# usb_smt.net
KiCad netlist of a schematic drawn in Altium Designer
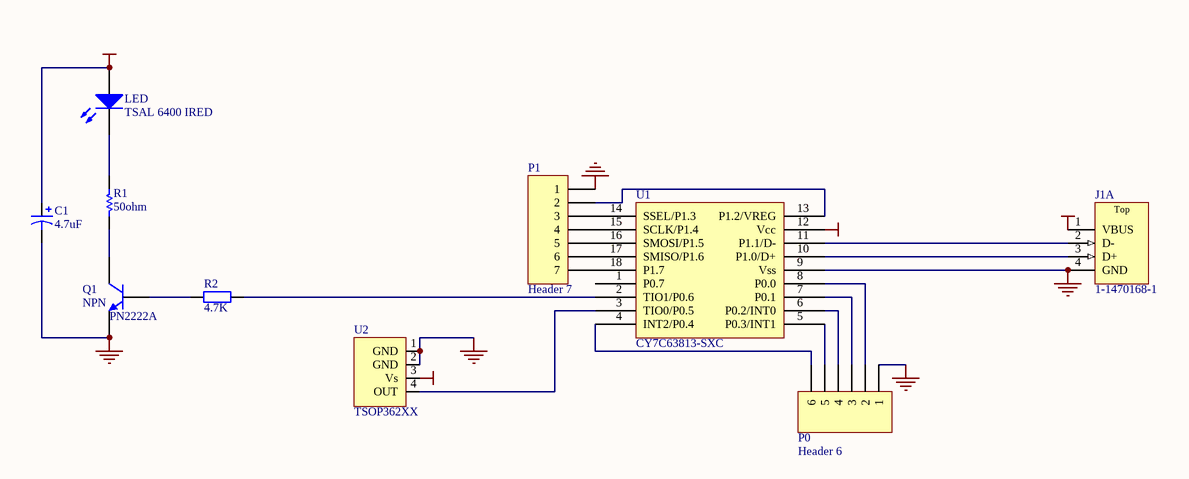
[diagram p0: usb_smt.SCHDOC]

(export (version "E")
  (design (tool "Eeschema 10.0.6"))
  (components
    (comp (ref "C1")
      (value "4.7uF")
      (footprint "TC3216-1206")
      (description "Polarized Capacitor (Radial)")
      (fields (field (name "Comment") "Cap Pol1") (field (name "PUBLISHER") "Altium Limited"))
      (libsource (lib "Miscellaneous Devices") (part "Cap Pol1"))
    )
    (comp (ref "J1")
      (value "1-1470168-1")
      (footprint "1470695")
      (description "USB 1.1, Right Angle, Thru-Hole, A Type, Receptacle, 4x4 Position, Stacked, Black")
      (fields (field (name "PUBLISHER") "Altium Limited"))
      (libsource (lib "AMP Serial Bus USB") (part "1-1470168-1"))
    )
    (comp (ref "LED")
      (value "TSAL 6400 IRED")
      (footprint "LED")
      (description "Typical INFRARED GaAs LED")
      (fields (field (name "PUBLISHER") "Altium Limited"))
      (libsource (lib "Miscellaneous Devices") (part "LED0"))
    )
    (comp (ref "P0")
      (value "Header 6")
      (footprint "HDR1X6")
      (description "Header, 6-Pin")
      (fields (field (name "PUBLISHER") "Altium Limited"))
      (libsource (lib "Miscellaneous Connectors") (part "Header 6"))
    )
    (comp (ref "P1")
      (value "Header 7")
      (footprint "HDR1X7")
      (description "Header, 7-Pin")
      (fields (field (name "PUBLISHER") "Altium Limited"))
      (libsource (lib "Miscellaneous Connectors") (part "Header 7"))
    )
    (comp (ref "Q1")
      (value "NPN")
      (footprint "SO-G3/D4.1")
      (description "NPN Bipolar Transistor")
      (fields (field (name "PUBLISHER") "Altium Limited"))
      (libsource (lib "Miscellaneous Devices") (part "NPN"))
    )
    (comp (ref "R1")
      (value "50ohm")
      (footprint "CR1608-0603")
      (description "Semiconductor Resistor")
      (fields (field (name "PUBLISHER") "Altium Limited"))
      (libsource (lib "Miscellaneous Devices") (part "Res Semi"))
    )
    (comp (ref "R2")
      (value "4.7K")
      (footprint "CR1608-0603")
      (description "Resistor")
      (fields (field (name "Comment") "Res2") (field (name "PUBLISHER") "Altium Limited"))
      (libsource (lib "Miscellaneous Devices") (part "Res2"))
    )
    (comp (ref "U1")
      (value "CY7C63813-SXC")
      (footprint "SO-G18/E6.2")
      (description "USB microcontroller, SMT")
      (libsource (lib "ir") (part "CY7C63813-SXC"))
    )
    (comp (ref "U2") (value "TSOP362XX") (footprint "TSOP 362XX") (libsource (lib "ir") (part "TSOP36238")))
  )
  (nets
    (net (code "1") (name "GND") (class "Default")
      (node (ref "C1") (pin "2") (pinfunction "2_2") (pintype "passive"))
      (node (ref "J1") (pin "4") (pinfunction "GND_4") (pintype "power_in"))
      (node (ref "P0") (pin "1") (pinfunction "1_1") (pintype "passive"))
      (node (ref "P1") (pin "1") (pinfunction "1_1") (pintype "passive"))
      (node (ref "Q1") (pin "3") (pinfunction "E_3") (pintype "passive"))
      (node (ref "U1") (pin "9") (pinfunction "Vss_9") (pintype "passive"))
      (node (ref "U2") (pin "1") (pinfunction "GND_1") (pintype "passive"))
      (node (ref "U2") (pin "2") (pinfunction "GND_2") (pintype "passive"))
    )
    (net (code "2") (name "Net-(J1A-D+)") (class "Default")
      (node (ref "J1") (pin "3") (pinfunction "D+_3") (pintype "input"))
      (node (ref "U1") (pin "10") (pinfunction "P1.0/D+_10") (pintype "passive"))
    )
    (net (code "3") (name "Net-(J1A-D-)") (class "Default")
      (node (ref "J1") (pin "2") (pinfunction "D-_2") (pintype "input"))
      (node (ref "U1") (pin "11") (pinfunction "P1.1/D-_11") (pintype "passive"))
    )
    (net (code "4") (name "Net-(LED-K)") (class "Default")
      (node (ref "LED") (pin "2") (pinfunction "K_2") (pintype "passive"))
      (node (ref "R1") (pin "2") (pinfunction "2_2") (pintype "passive"))
    )
    (net (code "5") (name "Net-(Q1-B)") (class "Default")
      (node (ref "Q1") (pin "2") (pinfunction "B_2") (pintype "passive"))
      (node (ref "R2") (pin "2") (pinfunction "2_2") (pintype "passive"))
    )
    (net (code "6") (name "Net-(Q1-C)") (class "Default")
      (node (ref "Q1") (pin "1") (pinfunction "C_1") (pintype "passive"))
      (node (ref "R1") (pin "1") (pinfunction "1_1") (pintype "passive"))
    )
    (net (code "7") (name "Net-(U1-INT2{slash}P0.4)") (class "Default")
      (node (ref "P0") (pin "6") (pinfunction "6_6") (pintype "passive"))
      (node (ref "U1") (pin "4") (pinfunction "INT2/P0.4_4") (pintype "passive"))
    )
    (net (code "8") (name "Net-(U1-P0.0)") (class "Default")
      (node (ref "P0") (pin "2") (pinfunction "2_2") (pintype "passive"))
      (node (ref "U1") (pin "8") (pinfunction "P0.0_8") (pintype "passive"))
    )
    (net (code "9") (name "Net-(U1-P0.1)") (class "Default")
      (node (ref "P0") (pin "3") (pinfunction "3_3") (pintype "passive"))
      (node (ref "U1") (pin "7") (pinfunction "P0.1_7") (pintype "passive"))
    )
    (net (code "10") (name "Net-(U1-P0.2{slash}INT0)") (class "Default")
      (node (ref "P0") (pin "4") (pinfunction "4_4") (pintype "passive"))
      (node (ref "U1") (pin "6") (pinfunction "P0.2/INT0_6") (pintype "passive"))
    )
    (net (code "11") (name "Net-(U1-P0.3{slash}INT1)") (class "Default")
      (node (ref "P0") (pin "5") (pinfunction "5_5") (pintype "passive"))
      (node (ref "U1") (pin "5") (pinfunction "P0.3/INT1_5") (pintype "passive"))
    )
    (net (code "12") (name "Net-(U1-P1.2{slash}VREG)") (class "Default")
      (node (ref "P1") (pin "2") (pinfunction "2_2") (pintype "passive"))
      (node (ref "U1") (pin "13") (pinfunction "P1.2/VREG_13") (pintype "passive"))
    )
    (net (code "13") (name "Net-(U1-P1.7)") (class "Default")
      (node (ref "P1") (pin "7") (pinfunction "7_7") (pintype "passive"))
      (node (ref "U1") (pin "18") (pinfunction "P1.7_18") (pintype "passive"))
    )
    (net (code "14") (name "Net-(U1-SCLK{slash}P1.4)") (class "Default")
      (node (ref "P1") (pin "4") (pinfunction "4_4") (pintype "passive"))
      (node (ref "U1") (pin "15") (pinfunction "SCLK/P1.4_15") (pintype "passive"))
    )
    (net (code "15") (name "Net-(U1-SMISO{slash}P1.6)") (class "Default")
      (node (ref "P1") (pin "6") (pinfunction "6_6") (pintype "passive"))
      (node (ref "U1") (pin "17") (pinfunction "SMISO/P1.6_17") (pintype "passive"))
    )
    (net (code "16") (name "Net-(U1-SMOSI{slash}P1.5)") (class "Default")
      (node (ref "P1") (pin "5") (pinfunction "5_5") (pintype "passive"))
      (node (ref "U1") (pin "16") (pinfunction "SMOSI/P1.5_16") (pintype "passive"))
    )
    (net (code "17") (name "Net-(U1-SSEL{slash}P1.3)") (class "Default")
      (node (ref "P1") (pin "3") (pinfunction "3_3") (pintype "passive"))
      (node (ref "U1") (pin "14") (pinfunction "SSEL/P1.3_14") (pintype "passive"))
    )
    (net (code "18") (name "Net-(U1-TIO0{slash}P0.5)") (class "Default")
      (node (ref "U1") (pin "3") (pinfunction "TIO0/P0.5_3") (pintype "passive"))
      (node (ref "U2") (pin "4") (pinfunction "OUT_4") (pintype "passive"))
    )
    (net (code "19") (name "Net-(U1-TIO1{slash}P0.6)") (class "Default")
      (node (ref "R2") (pin "1") (pinfunction "1_1") (pintype "passive"))
      (node (ref "U1") (pin "2") (pinfunction "TIO1/P0.6_2") (pintype "passive"))
    )
    (net (code "20") (name "VCC") (class "Default")
      (node (ref "C1") (pin "1") (pinfunction "1_1") (pintype "passive"))
      (node (ref "J1") (pin "1") (pinfunction "VBUS_1") (pintype "power_in"))
      (node (ref "LED") (pin "1") (pinfunction "A_1") (pintype "passive"))
      (node (ref "U1") (pin "12") (pinfunction "Vcc_12") (pintype "passive"))
      (node (ref "U2") (pin "3") (pinfunction "Vs_3") (pintype "passive"))
    )
    (net (code "21") (name "unconnected-(U1-P0.7-Pad1)") (class "Default")
      (node (ref "U1") (pin "1") (pinfunction "P0.7_1") (pintype "passive"))
    )
  )
)
